# task2_eagle.net
KiCad netlist of a schematic drawn in EAGLE
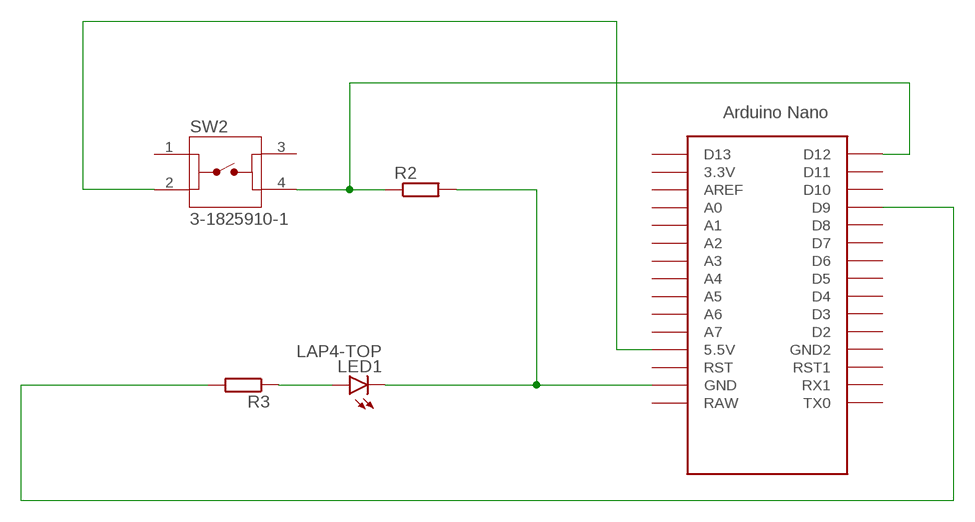
[diagram p0: schematic, sheet 1]

(export (version "E")
  (design (tool "Eeschema 10.0.6"))
  (components
    (comp (ref "LED1")
      (value "LAP4-TOP")
      (footprint "eagle-import:P47F-TOP")
      (libsource (lib "eagle-import") (part "P4-TOPLA"))
    )
    (comp (ref "R2")
      (value "R-EU_0207/12")
      (footprint "eagle-import:0207_12")
      (libsource (lib "eagle-import") (part "R-EU_0207/12"))
    )
    (comp (ref "R3")
      (value "R-EU_0207/12")
      (footprint "eagle-import:0207_12")
      (libsource (lib "eagle-import") (part "R-EU_0207/12"))
    )
    (comp (ref "SW2")
      (value "3-1825910-1")
      (footprint "eagle-import:TE_3-1825910-1")
      (fields (field (name "MF") "TE Connectivity"))
      (libsource (lib "eagle-import") (part "3-1825910-1"))
    )
    (comp (ref "U$1")
      (value "NANO")
      (footprint "eagle-import:NANO")
      (libsource (lib "eagle-import") (part "NANO"))
    )
  )
  (nets
    (net (code "1") (name "Net-(LED1-PadA)") (class "Default")
      (node (ref "LED1") (pin "A") (pinfunction "A_A") (pintype "passive"))
      (node (ref "R3") (pin "1") (pinfunction "1_1") (pintype "passive"))
    )
    (net (code "2") (name "Net-(LED1-PadC)") (class "Default")
      (node (ref "LED1") (pin "C") (pinfunction "C_C") (pintype "passive"))
      (node (ref "R2") (pin "2") (pinfunction "2_2") (pintype "passive"))
      (node (ref "U$1") (pin "GND") (pinfunction "GND_GND") (pintype "bidirectional"))
    )
    (net (code "3") (name "Net-(R2-Pad1)") (class "Default")
      (node (ref "R2") (pin "1") (pinfunction "1_1") (pintype "passive"))
      (node (ref "SW2") (pin "4") (pinfunction "4_4") (pintype "passive"))
      (node (ref "U$1") (pin "D12") (pinfunction "D12_D12") (pintype "bidirectional"))
    )
    (net (code "4") (name "Net-(R3-Pad2)") (class "Default")
      (node (ref "R3") (pin "2") (pinfunction "2_2") (pintype "passive"))
      (node (ref "U$1") (pin "D9") (pinfunction "D9_D9") (pintype "bidirectional"))
    )
    (net (code "5") (name "Net-(U$1-5.5V)") (class "Default")
      (node (ref "SW2") (pin "2") (pinfunction "2_2") (pintype "passive"))
      (node (ref "U$1") (pin "5V") (pinfunction "5.5V_5V") (pintype "bidirectional"))
    )
    (net (code "6") (name "unconnected-(SW2-Pad1)") (class "Default")
      (node (ref "SW2") (pin "1") (pinfunction "1_1") (pintype "passive"))
    )
    (net (code "7") (name "unconnected-(SW2-Pad3)") (class "Default")
      (node (ref "SW2") (pin "3") (pinfunction "3_3") (pintype "passive"))
    )
    (net (code "8") (name "unconnected-(U$1-GND2-PadGND1)") (class "Default")
      (node (ref "U$1") (pin "GND1") (pinfunction "GND2_GND1") (pintype "bidirectional"))
    )
    (net (code "9") (name "unconnected-(U$1-Pad3.3V)") (class "Default")
      (node (ref "U$1") (pin "3.3V") (pinfunction "3.3V_3.3V") (pintype "bidirectional"))
    )
    (net (code "10") (name "unconnected-(U$1-PadA0)") (class "Default")
      (node (ref "U$1") (pin "A0") (pinfunction "A0_A0") (pintype "bidirectional"))
    )
    (net (code "11") (name "unconnected-(U$1-PadA1)") (class "Default")
      (node (ref "U$1") (pin "A1") (pinfunction "A1_A1") (pintype "bidirectional"))
    )
    (net (code "12") (name "unconnected-(U$1-PadA2)") (class "Default")
      (node (ref "U$1") (pin "A2") (pinfunction "A2_A2") (pintype "bidirectional"))
    )
    (net (code "13") (name "unconnected-(U$1-PadA3)") (class "Default")
      (node (ref "U$1") (pin "A3") (pinfunction "A3_A3") (pintype "bidirectional"))
    )
    (net (code "14") (name "unconnected-(U$1-PadA4)") (class "Default")
      (node (ref "U$1") (pin "A4") (pinfunction "A4_A4") (pintype "bidirectional"))
    )
    (net (code "15") (name "unconnected-(U$1-PadA5)") (class "Default")
      (node (ref "U$1") (pin "A5") (pinfunction "A5_A5") (pintype "bidirectional"))
    )
    (net (code "16") (name "unconnected-(U$1-PadA6)") (class "Default")
      (node (ref "U$1") (pin "A6") (pinfunction "A6_A6") (pintype "bidirectional"))
    )
    (net (code "17") (name "unconnected-(U$1-PadA7)") (class "Default")
      (node (ref "U$1") (pin "A7") (pinfunction "A7_A7") (pintype "bidirectional"))
    )
    (net (code "18") (name "unconnected-(U$1-PadAREF)") (class "Default")
      (node (ref "U$1") (pin "AREF") (pinfunction "AREF_AREF") (pintype "bidirectional"))
    )
    (net (code "19") (name "unconnected-(U$1-PadD2)") (class "Default")
      (node (ref "U$1") (pin "D2") (pinfunction "D2_D2") (pintype "bidirectional"))
    )
    (net (code "20") (name "unconnected-(U$1-PadD3)") (class "Default")
      (node (ref "U$1") (pin "D3") (pinfunction "D3_D3") (pintype "bidirectional"))
    )
    (net (code "21") (name "unconnected-(U$1-PadD4)") (class "Default")
      (node (ref "U$1") (pin "D4") (pinfunction "D4_D4") (pintype "bidirectional"))
    )
    (net (code "22") (name "unconnected-(U$1-PadD5)") (class "Default")
      (node (ref "U$1") (pin "D5") (pinfunction "D5_D5") (pintype "bidirectional"))
    )
    (net (code "23") (name "unconnected-(U$1-PadD6)") (class "Default")
      (node (ref "U$1") (pin "D6") (pinfunction "D6_D6") (pintype "bidirectional"))
    )
    (net (code "24") (name "unconnected-(U$1-PadD7)") (class "Default")
      (node (ref "U$1") (pin "D7") (pinfunction "D7_D7") (pintype "bidirectional"))
    )
    (net (code "25") (name "unconnected-(U$1-PadD8)") (class "Default")
      (node (ref "U$1") (pin "D8") (pinfunction "D8_D8") (pintype "bidirectional"))
    )
    (net (code "26") (name "unconnected-(U$1-PadD10)") (class "Default")
      (node (ref "U$1") (pin "D10") (pinfunction "D10_D10") (pintype "bidirectional"))
    )
    (net (code "27") (name "unconnected-(U$1-PadD11)") (class "Default")
      (node (ref "U$1") (pin "D11") (pinfunction "D11_D11") (pintype "bidirectional"))
    )
    (net (code "28") (name "unconnected-(U$1-PadD13)") (class "Default")
      (node (ref "U$1") (pin "D13") (pinfunction "D13_D13") (pintype "bidirectional"))
    )
    (net (code "29") (name "unconnected-(U$1-PadICSP1)") (class "Default")
      (node (ref "U$1") (pin "ICSP1") (pinfunction "ICSP1_ICSP1") (pintype "bidirectional"))
    )
    (net (code "30") (name "unconnected-(U$1-PadICSP2)") (class "Default")
      (node (ref "U$1") (pin "ICSP2") (pinfunction "ICSP2_ICSP2") (pintype "bidirectional"))
    )
    (net (code "31") (name "unconnected-(U$1-PadICSP3)") (class "Default")
      (node (ref "U$1") (pin "ICSP3") (pinfunction "ICSP3_ICSP3") (pintype "bidirectional"))
    )
    (net (code "32") (name "unconnected-(U$1-PadICSP4)") (class "Default")
      (node (ref "U$1") (pin "ICSP4") (pinfunction "ICSP4_ICSP4") (pintype "bidirectional"))
    )
    (net (code "33") (name "unconnected-(U$1-PadICSP5)") (class "Default")
      (node (ref "U$1") (pin "ICSP5") (pinfunction "ICSP5_ICSP5") (pintype "bidirectional"))
    )
    (net (code "34") (name "unconnected-(U$1-PadICSP6)") (class "Default")
      (node (ref "U$1") (pin "ICSP6") (pinfunction "ICSP6_ICSP6") (pintype "bidirectional"))
    )
    (net (code "35") (name "unconnected-(U$1-PadRAW)") (class "Default")
      (node (ref "U$1") (pin "RAW") (pinfunction "RAW_RAW") (pintype "bidirectional"))
    )
    (net (code "36") (name "unconnected-(U$1-PadRST)") (class "Default")
      (node (ref "U$1") (pin "RST") (pinfunction "RST_RST") (pintype "bidirectional"))
    )
    (net (code "37") (name "unconnected-(U$1-PadRST1)") (class "Default")
      (node (ref "U$1") (pin "RST1") (pinfunction "RST1_RST1") (pintype "bidirectional"))
    )
    (net (code "38") (name "unconnected-(U$1-PadRX1)") (class "Default")
      (node (ref "U$1") (pin "RX1") (pinfunction "RX1_RX1") (pintype "bidirectional"))
    )
    (net (code "39") (name "unconnected-(U$1-PadTX0)") (class "Default")
      (node (ref "U$1") (pin "TX0") (pinfunction "TX0_TX0") (pintype "bidirectional"))
    )
  )
)
